# Controller_Part.net
KiCad netlist of a schematic drawn in Altium Designer
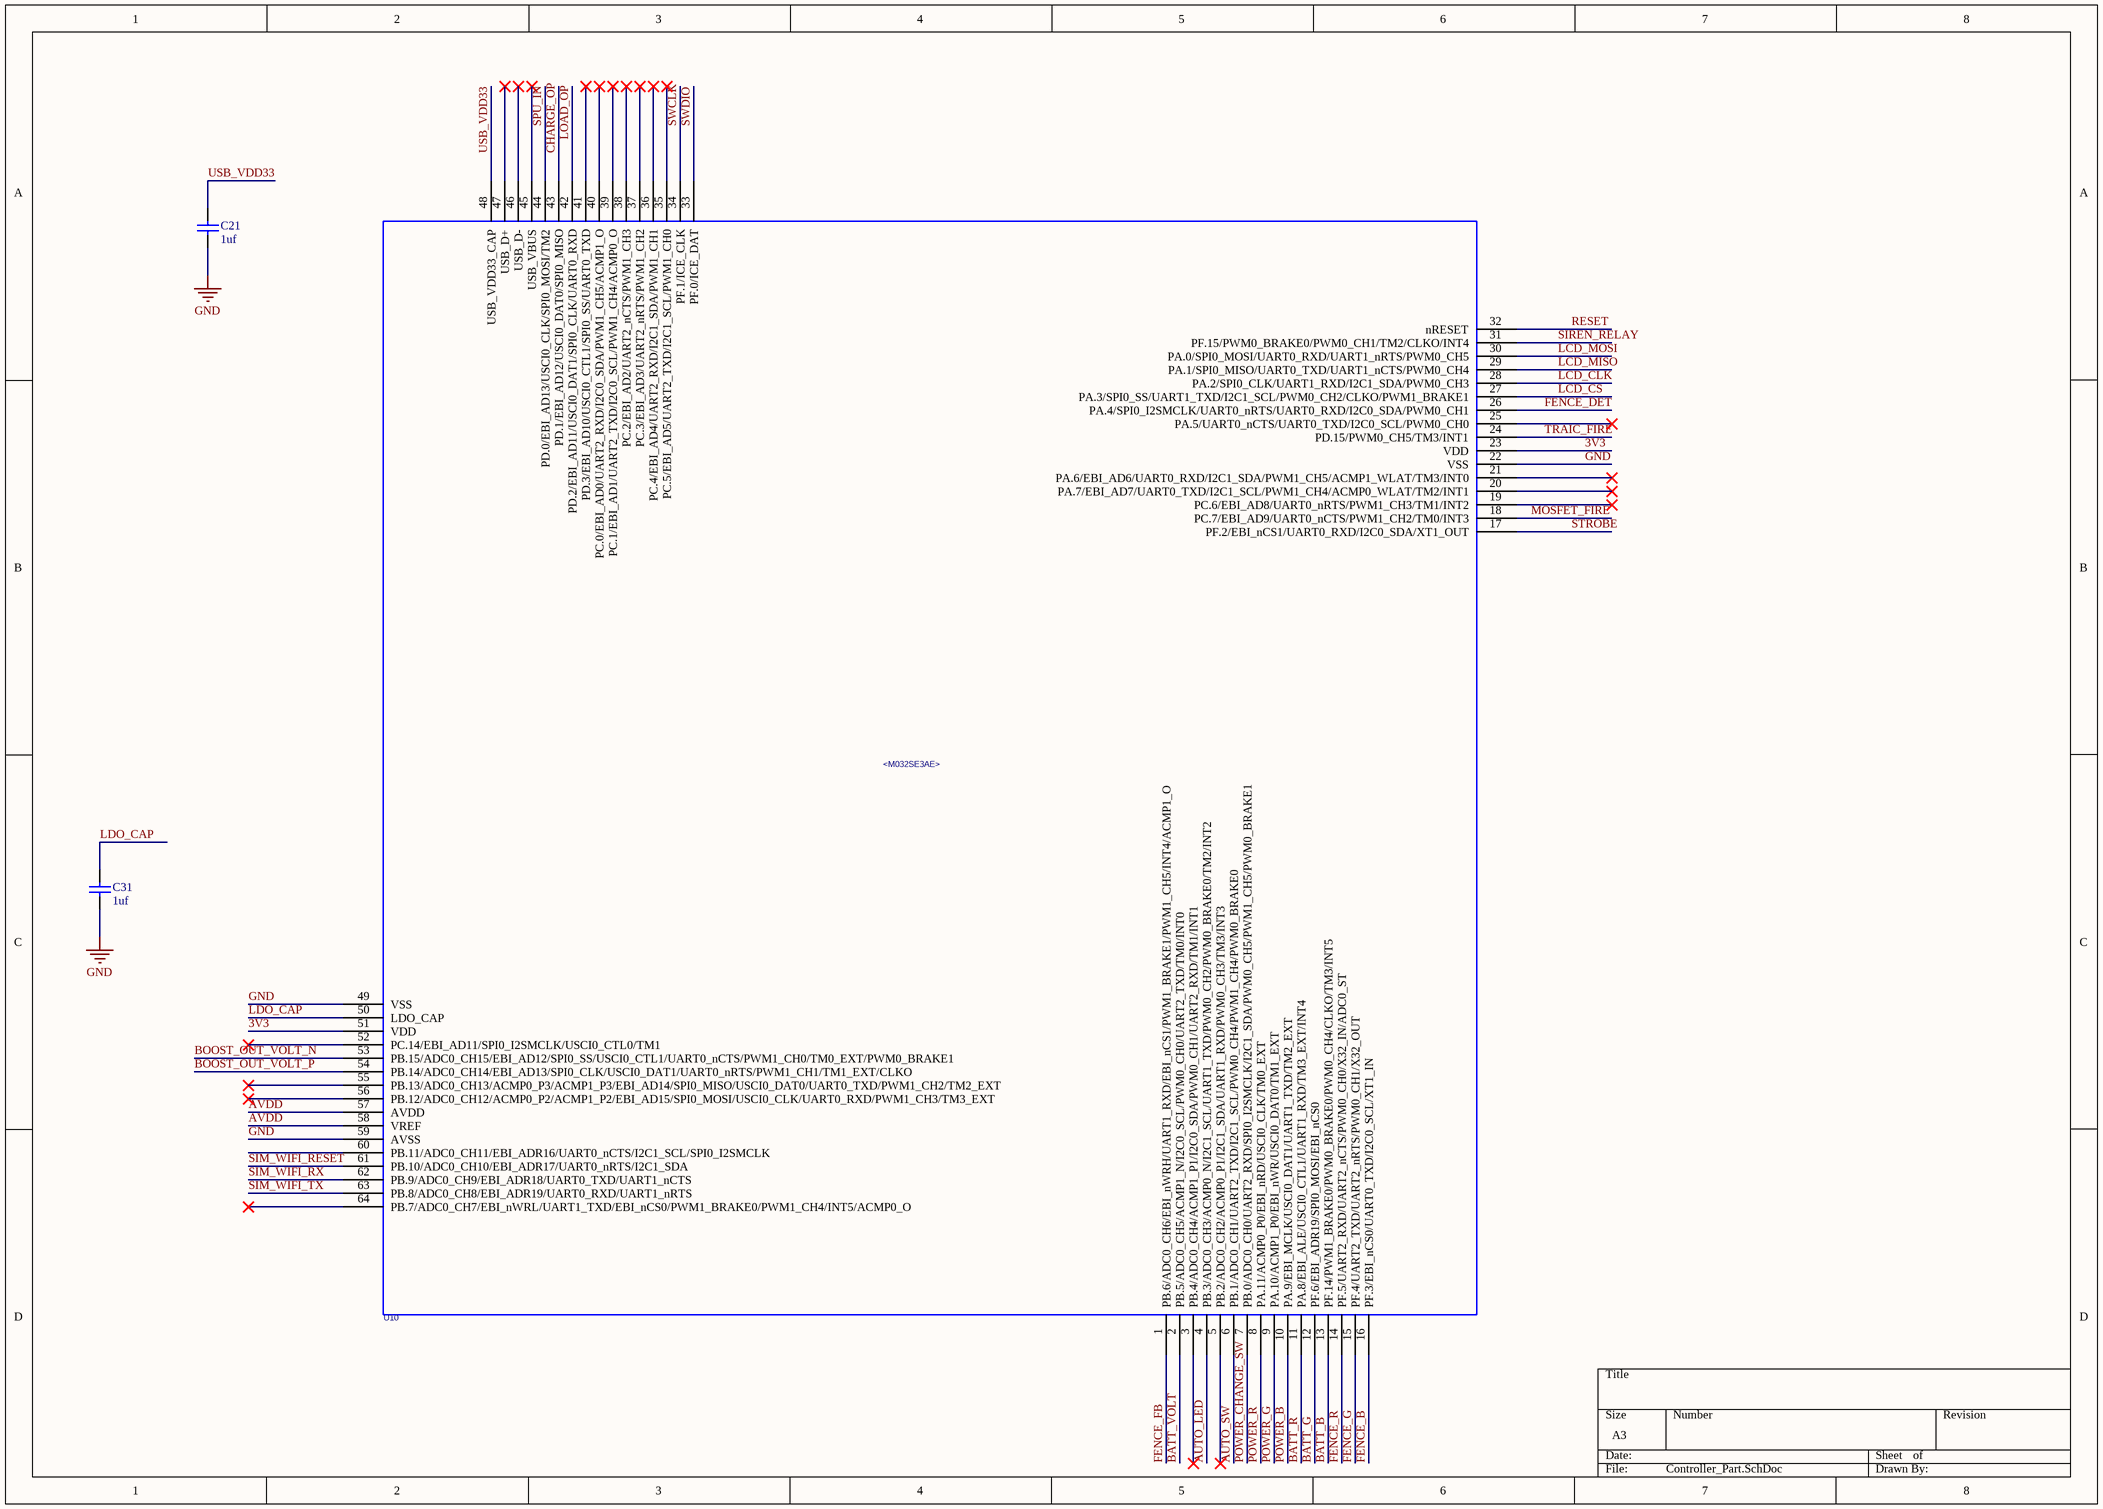
[diagram p0: Controller_Part.SchDoc]

(export (version "E")
  (design (tool "Eeschema 10.0.6"))
  (components
    (comp (ref "C21")
      (value "1uf")
      (footprint "0805")
      (description "Capacitor")
      (fields (field (name "Comment") "Cap") (field (name "PUBLISHER") "Altium Limited"))
      (libsource (lib "Miscellaneous Devices") (part "Cap"))
    )
    (comp (ref "C31")
      (value "1uf")
      (footprint "0805")
      (description "Capacitor")
      (fields (field (name "Comment") "Cap") (field (name "PUBLISHER") "Altium Limited"))
      (libsource (lib "Miscellaneous Devices") (part "Cap"))
    )
    (comp (ref "U10")
      (value "M031SE3AE")
      (footprint "LQFP-64")
      (fields (field (name "M031SE3AE") "<M032SE3AE>"))
      (libsource (lib "SchLib") (part "M031SE3AE"))
    )
  )
  (nets
    (net (code "1") (name "/3V3") (class "Default")
      (node (ref "U10") (pin "23") (pinfunction "VDD_23") (pintype "passive"))
      (node (ref "U10") (pin "51") (pinfunction "VDD_51") (pintype "passive"))
    )
    (net (code "2") (name "/AUTO_LED") (class "Default")
      (node (ref "U10") (pin "4") (pinfunction "PB.3/ADC0_CH3/ACMP0_N/I2C1_SCL/UART1_TXD/PWM0_CH2/PWM0_BRAKE0/TM2/INT2_4") (pintype "passive"))
    )
    (net (code "3") (name "/AUTO_SW") (class "Default")
      (node (ref "U10") (pin "6") (pinfunction "PB.1/ADC0_CH1/UART2_TXD/I2C1_SCL/PWM0_CH4/PWM1_CH4/PWM0_BRAKE0_6") (pintype "passive"))
    )
    (net (code "4") (name "/AVDD") (class "Default")
      (node (ref "U10") (pin "57") (pinfunction "AVDD_57") (pintype "passive"))
      (node (ref "U10") (pin "58") (pinfunction "VREF_58") (pintype "passive"))
    )
    (net (code "5") (name "/BATT_B") (class "Default")
      (node (ref "U10") (pin "13") (pinfunction "PF.14/PWM1_BRAKE0/PWM0_BRAKE0/PWM0_CH4/CLKO/TM3/INT5_13") (pintype "passive"))
    )
    (net (code "6") (name "/BATT_G") (class "Default")
      (node (ref "U10") (pin "12") (pinfunction "PF.6/EBI_ADR19/SPI0_MOSI/EBI_nCS0_12") (pintype "passive"))
    )
    (net (code "7") (name "/BATT_R") (class "Default")
      (node (ref "U10") (pin "11") (pinfunction "PA.8/EBI_ALE/USCI0_CTL1/UART1_RXD/TM3_EXT/INT4_11") (pintype "passive"))
    )
    (net (code "8") (name "/BATT_VOLT") (class "Default")
      (node (ref "U10") (pin "2") (pinfunction "PB.5/ADC0_CH5/ACMP1_N/I2C0_SCL/PWM0_CH0/UART2_TXD/TM0/INT0_2") (pintype "passive"))
    )
    (net (code "9") (name "/BOOST_OUT_VOLT_N") (class "Default")
      (node (ref "U10") (pin "53") (pinfunction "PB.15/ADC0_CH15/EBI_AD12/SPI0_SS/USCI0_CTL1/UART0_nCTS/PWM1_CH0/TM0_EXT/PWM0_BRAKE1_53") (pintype "passive"))
    )
    (net (code "10") (name "/BOOST_OUT_VOLT_P") (class "Default")
      (node (ref "U10") (pin "54") (pinfunction "PB.14/ADC0_CH14/EBI_AD13/SPI0_CLK/USCI0_DAT1/UART0_nRTS/PWM1_CH1/TM1_EXT/CLKO_54") (pintype "passive"))
    )
    (net (code "11") (name "/CHARGE_OP") (class "Default")
      (node (ref "U10") (pin "43") (pinfunction "PD.1/EBI_AD12/USCI0_DAT0/SPI0_MISO_43") (pintype "passive"))
    )
    (net (code "12") (name "/FENCE_B") (class "Default")
      (node (ref "U10") (pin "16") (pinfunction "PF.3/EBI_nCS0/UART0_TXD/I2C0_SCL/XT1_IN_16") (pintype "passive"))
    )
    (net (code "13") (name "/FENCE_DET") (class "Default")
      (node (ref "U10") (pin "26") (pinfunction "PA.4/SPI0_I2SMCLK/UART0_nRTS/UART0_RXD/I2C0_SDA/PWM0_CH1_26") (pintype "passive"))
    )
    (net (code "14") (name "/FENCE_FB") (class "Default")
      (node (ref "U10") (pin "1") (pinfunction "PB.6/ADC0_CH6/EBI_nWRH/UART1_RXD/EBI_nCS1/PWM1_BRAKE1/PWM1_CH5/INT4/ACMP1_O_1") (pintype "passive"))
    )
    (net (code "15") (name "/FENCE_G") (class "Default")
      (node (ref "U10") (pin "15") (pinfunction "PF.4/UART2_TXD/UART2_nRTS/PWM0_CH1/X32_OUT_15") (pintype "passive"))
    )
    (net (code "16") (name "/FENCE_R") (class "Default")
      (node (ref "U10") (pin "14") (pinfunction "PF.5/UART2_RXD/UART2_nCTS/PWM0_CH0/X32_IN/ADC0_ST_14") (pintype "passive"))
    )
    (net (code "17") (name "/LCD_CLK") (class "Default")
      (node (ref "U10") (pin "28") (pinfunction "PA.2/SPI0_CLK/UART1_RXD/I2C1_SDA/PWM0_CH3_28") (pintype "passive"))
    )
    (net (code "18") (name "/LCD_CS") (class "Default")
      (node (ref "U10") (pin "27") (pinfunction "PA.3/SPI0_SS/UART1_TXD/I2C1_SCL/PWM0_CH2/CLKO/PWM1_BRAKE1_27") (pintype "passive"))
    )
    (net (code "19") (name "/LCD_MISO") (class "Default")
      (node (ref "U10") (pin "29") (pinfunction "PA.1/SPI0_MISO/UART0_TXD/UART1_nCTS/PWM0_CH4_29") (pintype "passive"))
    )
    (net (code "20") (name "/LCD_MOSI") (class "Default")
      (node (ref "U10") (pin "30") (pinfunction "PA.0/SPI0_MOSI/UART0_RXD/UART1_nRTS/PWM0_CH5_30") (pintype "passive"))
    )
    (net (code "21") (name "/LDO_CAP") (class "Default")
      (node (ref "C31") (pin "2") (pinfunction "2_2") (pintype "passive"))
      (node (ref "U10") (pin "50") (pinfunction "LDO_CAP_50") (pintype "passive"))
    )
    (net (code "22") (name "/LOAD_OP") (class "Default")
      (node (ref "U10") (pin "42") (pinfunction "PD.2/EBI_AD11/USCI0_DAT1/SPI0_CLK/UART0_RXD_42") (pintype "passive"))
    )
    (net (code "23") (name "/MOSFET_FIRE") (class "Default")
      (node (ref "U10") (pin "18") (pinfunction "PC.7/EBI_AD9/UART0_nCTS/PWM1_CH2/TM0/INT3_18") (pintype "passive"))
    )
    (net (code "24") (name "/POWER_B") (class "Default")
      (node (ref "U10") (pin "10") (pinfunction "PA.9/EBI_MCLK/USCI0_DAT1/UART1_TXD/TM2_EXT_10") (pintype "passive"))
    )
    (net (code "25") (name "/POWER_CHANGE_SW") (class "Default")
      (node (ref "U10") (pin "7") (pinfunction "PB.0/ADC0_CH0/UART2_RXD/SPI0_I2SMCLK/I2C1_SDA/PWM0_CH5/PWM1_CH5/PWM0_BRAKE1_7") (pintype "passive"))
    )
    (net (code "26") (name "/POWER_G") (class "Default")
      (node (ref "U10") (pin "9") (pinfunction "PA.10/ACMP1_P0/EBI_nWR/USCI0_DAT0/TM1_EXT_9") (pintype "passive"))
    )
    (net (code "27") (name "/POWER_R") (class "Default")
      (node (ref "U10") (pin "8") (pinfunction "PA.11/ACMP0_P0/EBI_nRD/USCI0_CLK/TM0_EXT_8") (pintype "passive"))
    )
    (net (code "28") (name "/RESET") (class "Default")
      (node (ref "U10") (pin "32") (pinfunction "nRESET_32") (pintype "passive"))
    )
    (net (code "29") (name "/SIM_WIFI_RESET") (class "Default")
      (node (ref "U10") (pin "61") (pinfunction "PB.10/ADC0_CH10/EBI_ADR17/UART0_nRTS/I2C1_SDA_61") (pintype "passive"))
    )
    (net (code "30") (name "/SIM_WIFI_RX") (class "Default")
      (node (ref "U10") (pin "62") (pinfunction "PB.9/ADC0_CH9/EBI_ADR18/UART0_TXD/UART1_nCTS_62") (pintype "passive"))
    )
    (net (code "31") (name "/SIM_WIFI_TX") (class "Default")
      (node (ref "U10") (pin "63") (pinfunction "PB.8/ADC0_CH8/EBI_ADR19/UART0_RXD/UART1_nRTS_63") (pintype "passive"))
    )
    (net (code "32") (name "/SIREN_RELAY") (class "Default")
      (node (ref "U10") (pin "31") (pinfunction "PF.15/PWM0_BRAKE0/PWM0_CH1/TM2/CLKO/INT4_31") (pintype "passive"))
    )
    (net (code "33") (name "/SPU_IN") (class "Default")
      (node (ref "U10") (pin "44") (pinfunction "PD.0/EBI_AD13/USCI0_CLK/SPI0_MOSI/TM2_44") (pintype "passive"))
    )
    (net (code "34") (name "/STROBE") (class "Default")
      (node (ref "U10") (pin "17") (pinfunction "PF.2/EBI_nCS1/UART0_RXD/I2C0_SDA/XT1_OUT_17") (pintype "passive"))
    )
    (net (code "35") (name "/SWCLK") (class "Default")
      (node (ref "U10") (pin "34") (pinfunction "PF.1/ICE_CLK_34") (pintype "passive"))
    )
    (net (code "36") (name "/SWDIO") (class "Default")
      (node (ref "U10") (pin "33") (pinfunction "PF.0/ICE_DAT_33") (pintype "passive"))
    )
    (net (code "37") (name "/TRAIC_FIRE") (class "Default")
      (node (ref "U10") (pin "24") (pinfunction "PD.15/PWM0_CH5/TM3/INT1_24") (pintype "passive"))
    )
    (net (code "38") (name "/USB_VDD33") (class "Default")
      (node (ref "C21") (pin "2") (pinfunction "2_2") (pintype "passive"))
      (node (ref "U10") (pin "48") (pinfunction "USB_VDD33_CAP_48") (pintype "passive"))
    )
    (net (code "39") (name "GND") (class "Default")
      (node (ref "C21") (pin "1") (pinfunction "1_1") (pintype "passive"))
      (node (ref "C31") (pin "1") (pinfunction "1_1") (pintype "passive"))
      (node (ref "U10") (pin "22") (pinfunction "VSS_22") (pintype "passive"))
      (node (ref "U10") (pin "49") (pinfunction "VSS_49") (pintype "passive"))
      (node (ref "U10") (pin "59") (pinfunction "AVSS_59") (pintype "passive"))
    )
    (net (code "40") (name "unconnected-(U10-PA.5{slash}UART0_nCTS{slash}UART0_TXD{slash}I2C0_SCL{slash}PWM0_CH0-Pad25)") (class "Default")
      (node (ref "U10") (pin "25") (pinfunction "PA.5/UART0_nCTS/UART0_TXD/I2C0_SCL/PWM0_CH0_25") (pintype "passive+no_connect"))
    )
    (net (code "41") (name "unconnected-(U10-PA.6{slash}EBI_AD6{slash}UART0_RXD{slash}I2C1_SDA{slash}PWM1_CH5{slash}ACMP1_WLAT{slash}TM3{slash}INT0-Pad21)") (class "Default")
      (node (ref "U10") (pin "21") (pinfunction "PA.6/EBI_AD6/UART0_RXD/I2C1_SDA/PWM1_CH5/ACMP1_WLAT/TM3/INT0_21") (pintype "passive+no_connect"))
    )
    (net (code "42") (name "unconnected-(U10-PA.7{slash}EBI_AD7{slash}UART0_TXD{slash}I2C1_SCL{slash}PWM1_CH4{slash}ACMP0_WLAT{slash}TM2{slash}INT1-Pad20)") (class "Default")
      (node (ref "U10") (pin "20") (pinfunction "PA.7/EBI_AD7/UART0_TXD/I2C1_SCL/PWM1_CH4/ACMP0_WLAT/TM2/INT1_20") (pintype "passive+no_connect"))
    )
    (net (code "43") (name "unconnected-(U10-PB.2{slash}ADC0_CH2{slash}ACMP0_P1{slash}I2C1_SDA{slash}UART1_RXD{slash}PWM0_CH3{slash}TM3{slash}INT3-Pad5)") (class "Default")
      (node (ref "U10") (pin "5") (pinfunction "PB.2/ADC0_CH2/ACMP0_P1/I2C1_SDA/UART1_RXD/PWM0_CH3/TM3/INT3_5") (pintype "passive+no_connect"))
    )
    (net (code "44") (name "unconnected-(U10-PB.4{slash}ADC0_CH4{slash}ACMP1_P1{slash}I2C0_SDA{slash}PWM0_CH1{slash}UART2_RXD{slash}TM1{slash}INT1-Pad3)") (class "Default")
      (node (ref "U10") (pin "3") (pinfunction "PB.4/ADC0_CH4/ACMP1_P1/I2C0_SDA/PWM0_CH1/UART2_RXD/TM1/INT1_3") (pintype "passive+no_connect"))
    )
    (net (code "45") (name "unconnected-(U10-PB.7{slash}ADC0_CH7{slash}EBI_nWRL{slash}UART1_TXD{slash}EBI_nCS0{slash}PWM1_BRAKE0{slash}PWM1_CH4{slash}INT5{slash}ACMP0_O-Pad64)") (class "Default")
      (node (ref "U10") (pin "64") (pinfunction "PB.7/ADC0_CH7/EBI_nWRL/UART1_TXD/EBI_nCS0/PWM1_BRAKE0/PWM1_CH4/INT5/ACMP0_O_64") (pintype "passive+no_connect"))
    )
    (net (code "46") (name "unconnected-(U10-PB.11{slash}ADC0_CH11{slash}EBI_ADR16{slash}UART0_nCTS{slash}I2C1_SCL{slash}SPI0_I2SMCLK-Pad60)") (class "Default")
      (node (ref "U10") (pin "60") (pinfunction "PB.11/ADC0_CH11/EBI_ADR16/UART0_nCTS/I2C1_SCL/SPI0_I2SMCLK_60") (pintype "passive"))
    )
    (net (code "47") (name "unconnected-(U10-PB.12{slash}ADC0_CH12{slash}ACMP0_P2{slash}ACMP1_P2{slash}EBI_AD15{slash}SPI0_MOSI{slash}USCI0_CLK{slash}UART0_RXD{slash}PWM1_CH3{slash}TM3_EXT-Pad56)") (class "Default")
      (node (ref "U10") (pin "56") (pinfunction "PB.12/ADC0_CH12/ACMP0_P2/ACMP1_P2/EBI_AD15/SPI0_MOSI/USCI0_CLK/UART0_RXD/PWM1_CH3/TM3_EXT_56") (pintype "passive+no_connect"))
    )
    (net (code "48") (name "unconnected-(U10-PB.13{slash}ADC0_CH13{slash}ACMP0_P3{slash}ACMP1_P3{slash}EBI_AD14{slash}SPI0_MISO{slash}USCI0_DAT0{slash}UART0_TXD{slash}PWM1_CH2{slash}TM2_EXT-Pad55)") (class "Default")
      (node (ref "U10") (pin "55") (pinfunction "PB.13/ADC0_CH13/ACMP0_P3/ACMP1_P3/EBI_AD14/SPI0_MISO/USCI0_DAT0/UART0_TXD/PWM1_CH2/TM2_EXT_55") (pintype "passive+no_connect"))
    )
    (net (code "49") (name "unconnected-(U10-PC.0{slash}EBI_AD0{slash}UART2_RXD{slash}I2C0_SDA{slash}PWM1_CH5{slash}ACMP1_O-Pad40)") (class "Default")
      (node (ref "U10") (pin "40") (pinfunction "PC.0/EBI_AD0/UART2_RXD/I2C0_SDA/PWM1_CH5/ACMP1_O_40") (pintype "passive+no_connect"))
    )
    (net (code "50") (name "unconnected-(U10-PC.1{slash}EBI_AD1{slash}UART2_TXD{slash}I2C0_SCL{slash}PWM1_CH4{slash}ACMP0_O-Pad39)") (class "Default")
      (node (ref "U10") (pin "39") (pinfunction "PC.1/EBI_AD1/UART2_TXD/I2C0_SCL/PWM1_CH4/ACMP0_O_39") (pintype "passive+no_connect"))
    )
    (net (code "51") (name "unconnected-(U10-PC.2{slash}EBI_AD2{slash}UART2_nCTS{slash}PWM1_CH3-Pad38)") (class "Default")
      (node (ref "U10") (pin "38") (pinfunction "PC.2/EBI_AD2/UART2_nCTS/PWM1_CH3_38") (pintype "passive+no_connect"))
    )
    (net (code "52") (name "unconnected-(U10-PC.3{slash}EBI_AD3{slash}UART2_nRTS{slash}PWM1_CH2-Pad37)") (class "Default")
      (node (ref "U10") (pin "37") (pinfunction "PC.3/EBI_AD3/UART2_nRTS/PWM1_CH2_37") (pintype "passive+no_connect"))
    )
    (net (code "53") (name "unconnected-(U10-PC.4{slash}EBI_AD4{slash}UART2_RXD{slash}I2C1_SDA{slash}PWM1_CH1-Pad36)") (class "Default")
      (node (ref "U10") (pin "36") (pinfunction "PC.4/EBI_AD4/UART2_RXD/I2C1_SDA/PWM1_CH1_36") (pintype "passive+no_connect"))
    )
    (net (code "54") (name "unconnected-(U10-PC.5{slash}EBI_AD5{slash}UART2_TXD{slash}I2C1_SCL{slash}PWM1_CH0-Pad35)") (class "Default")
      (node (ref "U10") (pin "35") (pinfunction "PC.5/EBI_AD5/UART2_TXD/I2C1_SCL/PWM1_CH0_35") (pintype "passive+no_connect"))
    )
    (net (code "55") (name "unconnected-(U10-PC.6{slash}EBI_AD8{slash}UART0_nRTS{slash}PWM1_CH3{slash}TM1{slash}INT2-Pad19)") (class "Default")
      (node (ref "U10") (pin "19") (pinfunction "PC.6/EBI_AD8/UART0_nRTS/PWM1_CH3/TM1/INT2_19") (pintype "passive+no_connect"))
    )
    (net (code "56") (name "unconnected-(U10-PC.14{slash}EBI_AD11{slash}SPI0_I2SMCLK{slash}USCI0_CTL0{slash}TM1-Pad52)") (class "Default")
      (node (ref "U10") (pin "52") (pinfunction "PC.14/EBI_AD11/SPI0_I2SMCLK/USCI0_CTL0/TM1_52") (pintype "passive+no_connect"))
    )
    (net (code "57") (name "unconnected-(U10-PD.3{slash}EBI_AD10{slash}USCI0_CTL1{slash}SPI0_SS{slash}UART0_TXD-Pad41)") (class "Default")
      (node (ref "U10") (pin "41") (pinfunction "PD.3/EBI_AD10/USCI0_CTL1/SPI0_SS/UART0_TXD_41") (pintype "passive+no_connect"))
    )
    (net (code "58") (name "unconnected-(U10-USB_D+-Pad47)") (class "Default")
      (node (ref "U10") (pin "47") (pinfunction "USB_D+_47") (pintype "passive+no_connect"))
    )
    (net (code "59") (name "unconnected-(U10-USB_D--Pad46)") (class "Default")
      (node (ref "U10") (pin "46") (pinfunction "USB_D-_46") (pintype "passive+no_connect"))
    )
    (net (code "60") (name "unconnected-(U10-USB_VBUS-Pad45)") (class "Default")
      (node (ref "U10") (pin "45") (pinfunction "USB_VBUS_45") (pintype "passive+no_connect"))
    )
  )
)
